# Blueshift_V1.net
KiCad netlist of a schematic drawn in EAGLE
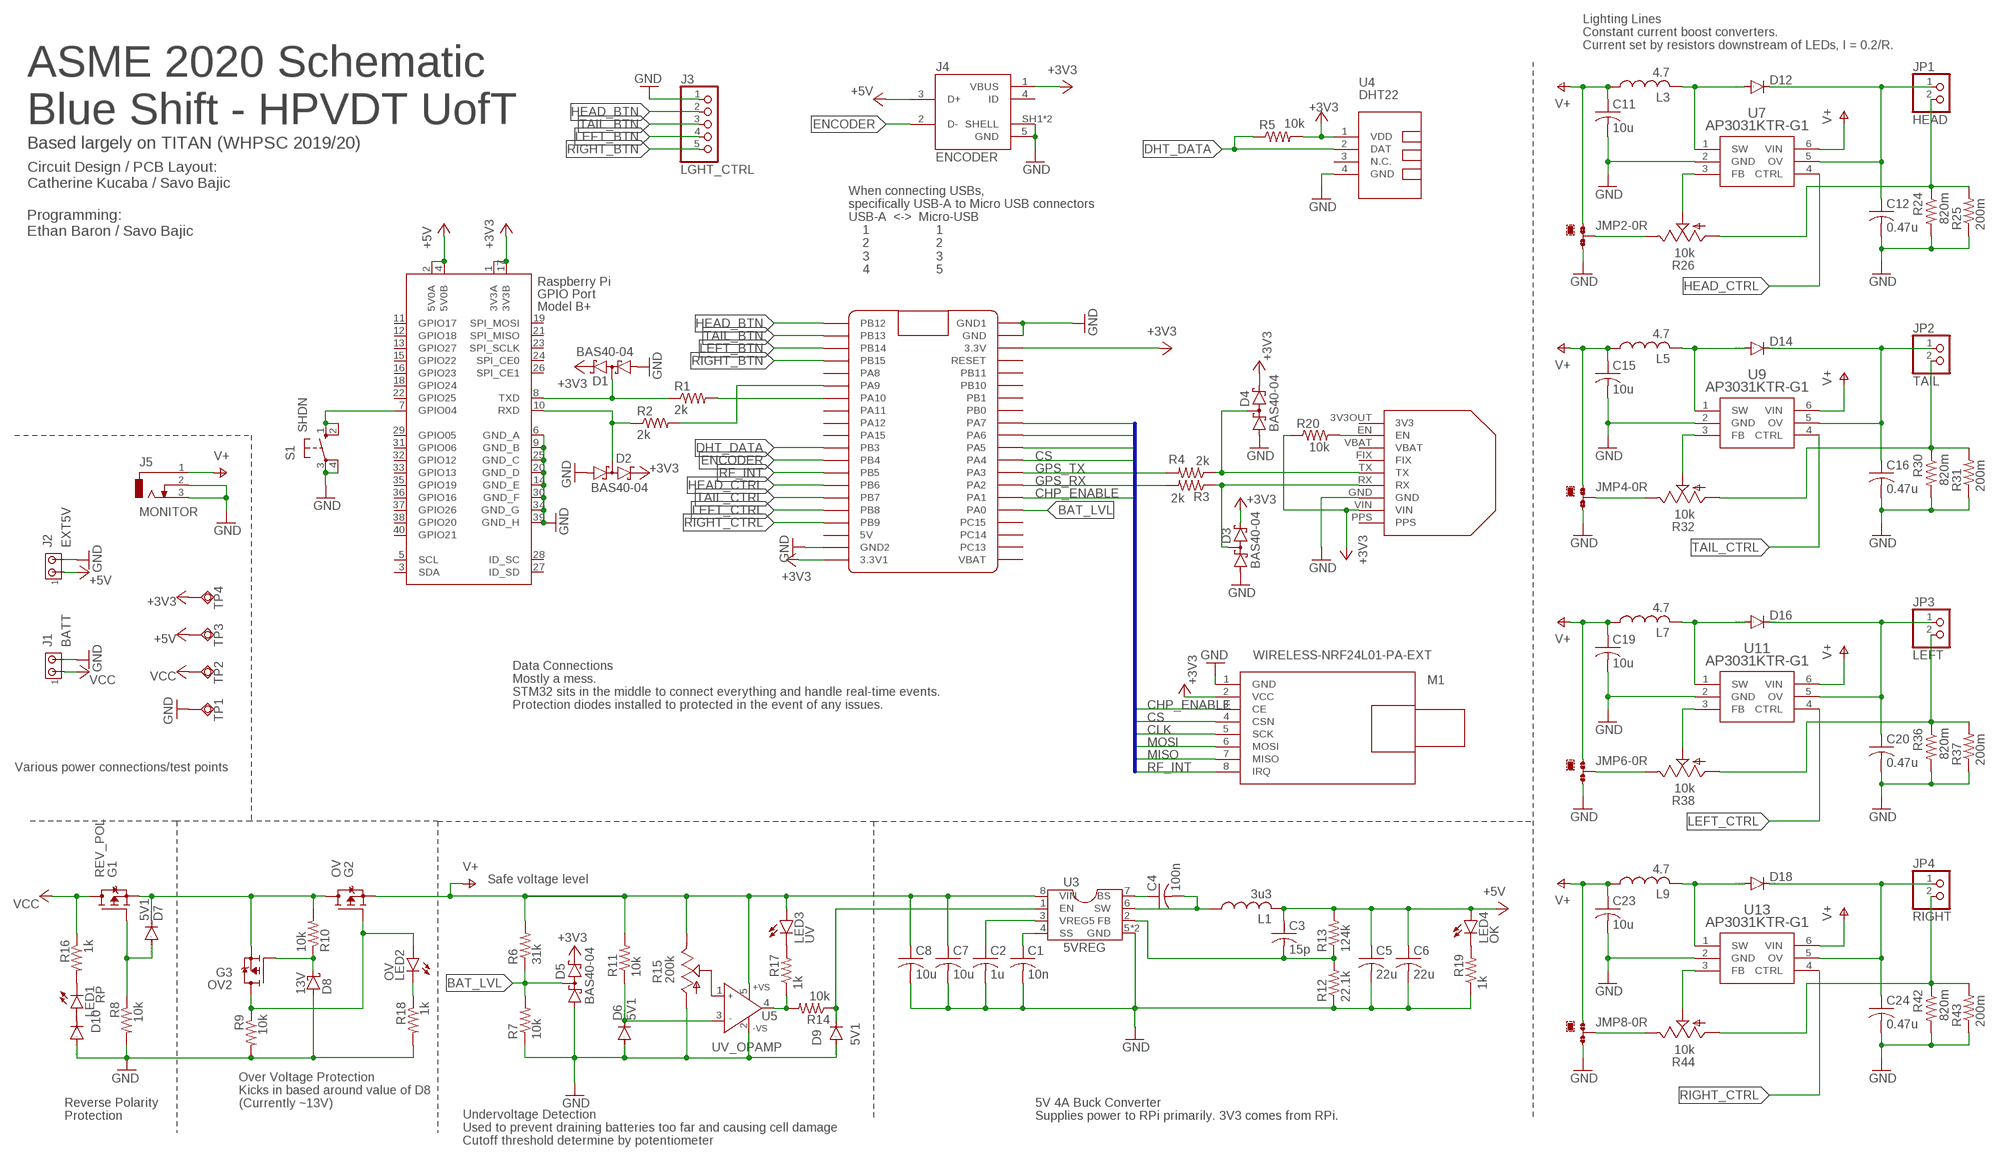
[diagram p0: schematic, sheet 1]

(export (version "E")
  (design (tool "Eeschema 10.0.6"))
  (components
    (comp (ref "C1")
      (value "10n")
      (footprint "eagle-import:C0402")
      (libsource (lib "eagle-import") (part "C-USC0402"))
    )
    (comp (ref "C2")
      (value "1u")
      (footprint "eagle-import:C0402")
      (libsource (lib "eagle-import") (part "C-USC0402"))
    )
    (comp (ref "C3")
      (value "15p")
      (footprint "eagle-import:C0402")
      (libsource (lib "eagle-import") (part "C-USC0402"))
    )
    (comp (ref "C4")
      (value "100n")
      (footprint "eagle-import:C0402")
      (libsource (lib "eagle-import") (part "C-USC0402"))
    )
    (comp (ref "C5")
      (value "22u")
      (footprint "eagle-import:C0805")
      (libsource (lib "eagle-import") (part "C-USC0805"))
    )
    (comp (ref "C6")
      (value "22u")
      (footprint "eagle-import:C0805")
      (libsource (lib "eagle-import") (part "C-USC0805"))
    )
    (comp (ref "C7")
      (value "10u")
      (footprint "eagle-import:C0805")
      (libsource (lib "eagle-import") (part "C-USC0805"))
    )
    (comp (ref "C8")
      (value "10u")
      (footprint "eagle-import:C0805")
      (libsource (lib "eagle-import") (part "C-USC0805"))
    )
    (comp (ref "C11")
      (value "10u")
      (footprint "eagle-import:C1206K")
      (libsource (lib "eagle-import") (part "C-USC1206K"))
    )
    (comp (ref "C12")
      (value "0.47u")
      (footprint "eagle-import:C1206K")
      (libsource (lib "eagle-import") (part "C-USC1206K"))
    )
    (comp (ref "C15")
      (value "10u")
      (footprint "eagle-import:C1206K")
      (libsource (lib "eagle-import") (part "C-USC1206K"))
    )
    (comp (ref "C16")
      (value "0.47u")
      (footprint "eagle-import:C1206K")
      (libsource (lib "eagle-import") (part "C-USC1206K"))
    )
    (comp (ref "C19")
      (value "10u")
      (footprint "eagle-import:C1206K")
      (libsource (lib "eagle-import") (part "C-USC1206K"))
    )
    (comp (ref "C20")
      (value "0.47u")
      (footprint "eagle-import:C1206K")
      (libsource (lib "eagle-import") (part "C-USC1206K"))
    )
    (comp (ref "C23")
      (value "10u")
      (footprint "eagle-import:C1206K")
      (libsource (lib "eagle-import") (part "C-USC1206K"))
    )
    (comp (ref "C24")
      (value "0.47u")
      (footprint "eagle-import:C1206K")
      (libsource (lib "eagle-import") (part "C-USC1206K"))
    )
    (comp (ref "D1")
      (value "BAS40-04")
      (footprint "eagle-import:SOT23")
      (libsource (lib "eagle-import") (part "BAS40-04"))
    )
    (comp (ref "D2")
      (value "BAS40-04")
      (footprint "eagle-import:SOT23")
      (libsource (lib "eagle-import") (part "BAS40-04"))
    )
    (comp (ref "D3")
      (value "BAS40-04")
      (footprint "eagle-import:SOT23")
      (libsource (lib "eagle-import") (part "BAS40-04"))
    )
    (comp (ref "D4")
      (value "BAS40-04")
      (footprint "eagle-import:SOT23")
      (libsource (lib "eagle-import") (part "BAS40-04"))
    )
    (comp (ref "D5")
      (value "BAS40-04")
      (footprint "eagle-import:SOT23")
      (libsource (lib "eagle-import") (part "BAS40-04"))
    )
    (comp (ref "D6")
      (value "5V1")
      (footprint "eagle-import:SOD323-R")
      (libsource (lib "eagle-import") (part "DIODE-SOD323-R"))
    )
    (comp (ref "D7")
      (value "5V1")
      (footprint "eagle-import:SOD323-R")
      (libsource (lib "eagle-import") (part "DIODE-SOD323-R"))
    )
    (comp (ref "D8")
      (value "13V")
      (footprint "eagle-import:SOT23")
      (libsource (lib "eagle-import") (part "BAS70"))
    )
    (comp (ref "D9")
      (value "5V1")
      (footprint "eagle-import:SOD323-R")
      (libsource (lib "eagle-import") (part "DIODE-SOD323-R"))
    )
    (comp (ref "D10")
      (value "DIODE-SOD80C")
      (footprint "eagle-import:SOD80C")
      (libsource (lib "eagle-import") (part "DIODE-SOD80C"))
    )
    (comp (ref "D12")
      (value "DIODE-DO-214AC")
      (footprint "eagle-import:DO-214AC")
      (libsource (lib "eagle-import") (part "DIODE-DO-214AC"))
    )
    (comp (ref "D14")
      (value "DIODE-DO-214AC")
      (footprint "eagle-import:DO-214AC")
      (libsource (lib "eagle-import") (part "DIODE-DO-214AC"))
    )
    (comp (ref "D16")
      (value "DIODE-DO-214AC")
      (footprint "eagle-import:DO-214AC")
      (libsource (lib "eagle-import") (part "DIODE-DO-214AC"))
    )
    (comp (ref "D18")
      (value "DIODE-DO-214AC")
      (footprint "eagle-import:DO-214AC")
      (libsource (lib "eagle-import") (part "DIODE-DO-214AC"))
    )
    (comp (ref "G1")
      (value "REV_POL")
      (footprint "eagle-import:TSOP-6")
      (libsource (lib "eagle-import") (part "SI3493DDV-T1-GE3"))
    )
    (comp (ref "G2")
      (value "OV")
      (footprint "eagle-import:TSOP-6")
      (libsource (lib "eagle-import") (part "SI3493DDV-T1-GE3"))
    )
    (comp (ref "G3")
      (value "OV2")
      (footprint "eagle-import:TSOP-6")
      (libsource (lib "eagle-import") (part "SI3493DDV-T1-GE3"))
    )
    (comp (ref "J1")
      (value "BATT")
      (footprint "eagle-import:1X2MTA")
      (libsource (lib "eagle-import") (part "MTA02-156"))
    )
    (comp (ref "J2")
      (value "EXT5V")
      (footprint "eagle-import:1X2MTA")
      (libsource (lib "eagle-import") (part "MTA02-156"))
    )
    (comp (ref "J3")
      (value "LGHT_CTRL")
      (footprint "eagle-import:1X05")
      (libsource (lib "eagle-import") (part "PINHD-1X5"))
    )
    (comp (ref "J4")
      (value "ENCODER")
      (footprint "eagle-import:TE_2172034-1")
      (fields
        (field (name "COMMENT") "2172034-1")
        (field (name "DIGI-KEY_PART_NUMBER") "A135698-ND")
        (field (name "MF") "TE Connectivity")
      )
      (libsource (lib "eagle-import") (part "2172034-1"))
    )
    (comp (ref "J5")
      (value "MONITOR")
      (footprint "eagle-import:DCJ0303")
      (libsource (lib "eagle-import") (part "DCJ0303"))
    )
    (comp (ref "JMP2")
      (value "0R-JUMPA")
      (footprint "eagle-import:A0R-JMP")
      (libsource (lib "eagle-import") (part "0R-JUMPA"))
    )
    (comp (ref "JMP4")
      (value "0R-JUMPA")
      (footprint "eagle-import:A0R-JMP")
      (libsource (lib "eagle-import") (part "0R-JUMPA"))
    )
    (comp (ref "JMP6")
      (value "0R-JUMPA")
      (footprint "eagle-import:A0R-JMP")
      (libsource (lib "eagle-import") (part "0R-JUMPA"))
    )
    (comp (ref "JMP8")
      (value "0R-JUMPA")
      (footprint "eagle-import:A0R-JMP")
      (libsource (lib "eagle-import") (part "0R-JUMPA"))
    )
    (comp (ref "JP1")
      (value "HEAD")
      (footprint "eagle-import:1X02")
      (libsource (lib "eagle-import") (part "PINHD-1X2"))
    )
    (comp (ref "JP2")
      (value "TAIL")
      (footprint "eagle-import:1X02")
      (libsource (lib "eagle-import") (part "PINHD-1X2"))
    )
    (comp (ref "JP3")
      (value "LEFT")
      (footprint "eagle-import:1X02")
      (libsource (lib "eagle-import") (part "PINHD-1X2"))
    )
    (comp (ref "JP4")
      (value "RIGHT")
      (footprint "eagle-import:1X02")
      (libsource (lib "eagle-import") (part "PINHD-1X2"))
    )
    (comp (ref "L1")
      (value "3u3")
      (footprint "eagle-import:SDES064T")
      (libsource (lib "eagle-import") (part "SDES064T-3R3MS"))
    )
    (comp (ref "L3")
      (value "4.7")
      (footprint "eagle-import:INDDFN600X600X280-2N")
      (libsource (lib "eagle-import") (part "NR6028NR6028"))
    )
    (comp (ref "L5")
      (value "4.7")
      (footprint "eagle-import:INDDFN600X600X280-2N")
      (libsource (lib "eagle-import") (part "NR6028NR6028"))
    )
    (comp (ref "L7")
      (value "4.7")
      (footprint "eagle-import:INDDFN600X600X280-2N")
      (libsource (lib "eagle-import") (part "NR6028NR6028"))
    )
    (comp (ref "L9")
      (value "4.7")
      (footprint "eagle-import:INDDFN600X600X280-2N")
      (libsource (lib "eagle-import") (part "NR6028NR6028"))
    )
    (comp (ref "LED1")
      (value "RP")
      (footprint "eagle-import:SML0805")
      (libsource (lib "eagle-import") (part "LEDSML0805"))
    )
    (comp (ref "LED2")
      (value "OV")
      (footprint "eagle-import:SML0805")
      (libsource (lib "eagle-import") (part "LEDSML0805"))
    )
    (comp (ref "LED3")
      (value "UV")
      (footprint "eagle-import:SML0805")
      (libsource (lib "eagle-import") (part "LEDSML0805"))
    )
    (comp (ref "LED4")
      (value "OK")
      (footprint "eagle-import:SML0805")
      (libsource (lib "eagle-import") (part "LEDSML0805"))
    )
    (comp (ref "M1")
      (value "WIRELESS-NRF24L01-PA-EXT")
      (footprint "eagle-import:WIRELESS-NRF24L01-PA-EXT")
      (libsource (lib "eagle-import") (part "WIRELESS-NRF24L01-PA-EXT"))
    )
    (comp (ref "M2")
      (value "ULTIMATE-GPS")
      (footprint "eagle-import:ULTIMATE_GPS")
      (libsource (lib "eagle-import") (part "ULTIMATE-GPS"))
    )
    (comp (ref "R1")
      (value "2k")
      (footprint "eagle-import:R0402")
      (libsource (lib "eagle-import") (part "R-US_R0402"))
    )
    (comp (ref "R2")
      (value "2k")
      (footprint "eagle-import:R0402")
      (libsource (lib "eagle-import") (part "R-US_R0402"))
    )
    (comp (ref "R3")
      (value "2k")
      (footprint "eagle-import:R0402")
      (libsource (lib "eagle-import") (part "R-US_R0402"))
    )
    (comp (ref "R4")
      (value "2k")
      (footprint "eagle-import:R0402")
      (libsource (lib "eagle-import") (part "R-US_R0402"))
    )
    (comp (ref "R5")
      (value "10k")
      (footprint "eagle-import:R0402")
      (libsource (lib "eagle-import") (part "R-US_R0402"))
    )
    (comp (ref "R6")
      (value "31k")
      (footprint "eagle-import:R0402")
      (libsource (lib "eagle-import") (part "R-US_R0402"))
    )
    (comp (ref "R7")
      (value "10k")
      (footprint "eagle-import:R0402")
      (libsource (lib "eagle-import") (part "R-US_R0402"))
    )
    (comp (ref "R8")
      (value "10k")
      (footprint "eagle-import:R0402")
      (libsource (lib "eagle-import") (part "R-US_R0402"))
    )
    (comp (ref "R9")
      (value "10k")
      (footprint "eagle-import:R0402")
      (libsource (lib "eagle-import") (part "R-US_R0402"))
    )
    (comp (ref "R10")
      (value "10k")
      (footprint "eagle-import:R0402")
      (libsource (lib "eagle-import") (part "R-US_R0402"))
    )
    (comp (ref "R11")
      (value "10k")
      (footprint "eagle-import:R0402")
      (libsource (lib "eagle-import") (part "R-US_R0402"))
    )
    (comp (ref "R12")
      (value "22.1k")
      (footprint "eagle-import:R0402")
      (libsource (lib "eagle-import") (part "R-US_R0402"))
    )
    (comp (ref "R13")
      (value "124k")
      (footprint "eagle-import:R0402")
      (libsource (lib "eagle-import") (part "R-US_R0402"))
    )
    (comp (ref "R14")
      (value "10k")
      (footprint "eagle-import:R0402")
      (libsource (lib "eagle-import") (part "R-US_R0402"))
    )
    (comp (ref "R15")
      (value "200k")
      (footprint "eagle-import:CA6V")
      (libsource (lib "eagle-import") (part "TRIM_US-CA6V"))
    )
    (comp (ref "R16")
      (value "1k")
      (footprint "eagle-import:R0402")
      (libsource (lib "eagle-import") (part "R-US_R0402"))
    )
    (comp (ref "R17")
      (value "1k")
      (footprint "eagle-import:R0402")
      (libsource (lib "eagle-import") (part "R-US_R0402"))
    )
    (comp (ref "R18")
      (value "1k")
      (footprint "eagle-import:R0402")
      (libsource (lib "eagle-import") (part "R-US_R0402"))
    )
    (comp (ref "R19")
      (value "1k")
      (footprint "eagle-import:R0402")
      (libsource (lib "eagle-import") (part "R-US_R0402"))
    )
    (comp (ref "R20")
      (value "10k")
      (footprint "eagle-import:R0402")
      (libsource (lib "eagle-import") (part "R-US_R0402"))
    )
    (comp (ref "R24")
      (value "820m")
      (footprint "eagle-import:R0603")
      (libsource (lib "eagle-import") (part "R-US_R0603"))
    )
    (comp (ref "R25")
      (value "200m")
      (footprint "eagle-import:R0805")
      (libsource (lib "eagle-import") (part "R-US_R0805"))
    )
    (comp (ref "R26")
      (value "10k")
      (footprint "eagle-import:RJ9W")
      (libsource (lib "eagle-import") (part "TRIM_US-RJ9W"))
    )
    (comp (ref "R30")
      (value "820m")
      (footprint "eagle-import:R0603")
      (libsource (lib "eagle-import") (part "R-US_R0603"))
    )
    (comp (ref "R31")
      (value "200m")
      (footprint "eagle-import:R0805")
      (libsource (lib "eagle-import") (part "R-US_R0805"))
    )
    (comp (ref "R32")
      (value "10k")
      (footprint "eagle-import:RJ9W")
      (libsource (lib "eagle-import") (part "TRIM_US-RJ9W"))
    )
    (comp (ref "R36")
      (value "820m")
      (footprint "eagle-import:R0603")
      (libsource (lib "eagle-import") (part "R-US_R0603"))
    )
    (comp (ref "R37")
      (value "200m")
      (footprint "eagle-import:R0805")
      (libsource (lib "eagle-import") (part "R-US_R0805"))
    )
    (comp (ref "R38")
      (value "10k")
      (footprint "eagle-import:RJ9W")
      (libsource (lib "eagle-import") (part "TRIM_US-RJ9W"))
    )
    (comp (ref "R42")
      (value "820m")
      (footprint "eagle-import:R0603")
      (libsource (lib "eagle-import") (part "R-US_R0603"))
    )
    (comp (ref "R43")
      (value "200m")
      (footprint "eagle-import:R0805")
      (libsource (lib "eagle-import") (part "R-US_R0805"))
    )
    (comp (ref "R44")
      (value "10k")
      (footprint "eagle-import:RJ9W")
      (libsource (lib "eagle-import") (part "TRIM_US-RJ9W"))
    )
    (comp (ref "S1")
      (value "SHDN")
      (footprint "eagle-import:B3F-10XX")
      (fields (field (name "MPN") "B3F-1000"))
      (libsource (lib "eagle-import") (part "10-XX"))
    )
    (comp (ref "TP1")
      (value "TPSQTP20SQ")
      (footprint "eagle-import:TP20SQ")
      (libsource (lib "eagle-import") (part "TPSQTP20SQ"))
    )
    (comp (ref "TP2")
      (value "TPSQTP20R")
      (footprint "eagle-import:TP20R")
      (libsource (lib "eagle-import") (part "TPSQTP20R"))
    )
    (comp (ref "TP3")
      (value "TPSQTP20R")
      (footprint "eagle-import:TP20R")
      (libsource (lib "eagle-import") (part "TPSQTP20R"))
    )
    (comp (ref "TP4")
      (value "TPSQTP20R")
      (footprint "eagle-import:TP20R")
      (libsource (lib "eagle-import") (part "TPSQTP20R"))
    )
    (comp (ref "U1")
      (value "RASPI_HAT")
      (footprint "eagle-import:RASPI_BOARD_B+HAT_CF")
      (libsource (lib "eagle-import") (part "RASPI_HAT"))
    )
    (comp (ref "U2")
      (value "BLUEPILL")
      (footprint "eagle-import:BLUE_PILL")
      (libsource (lib "eagle-import") (part "BLUE_PILL"))
    )
    (comp (ref "U3")
      (value "5VREG")
      (footprint "eagle-import:SO-8EP")
      (libsource (lib "eagle-import") (part "AP65450SP-13"))
    )
    (comp (ref "U4")
      (value "DHT22")
      (footprint "eagle-import:TEMP-HUM-SENSOR-DHT22")
      (libsource (lib "eagle-import") (part "TEMP-HUM-SENSOR-DHT22"))
    )
    (comp (ref "U5")
      (value "UV_OPAMP")
      (footprint "eagle-import:SOT-753")
      (libsource (lib "eagle-import") (part "TA75S558F,LF"))
    )
    (comp (ref "U7")
      (value "AP3031KTR-G1")
      (footprint "eagle-import:SOT23-6")
      (fields (field (name "MANUFACTURER_PART_NUMBER") "AP3031KTRG1"))
      (libsource (lib "eagle-import") (part "AP3031KTR-G1"))
    )
    (comp (ref "U9")
      (value "AP3031KTR-G1")
      (footprint "eagle-import:SOT23-6")
      (fields (field (name "MANUFACTURER_PART_NUMBER") "AP3031KTRG1"))
      (libsource (lib "eagle-import") (part "AP3031KTR-G1"))
    )
    (comp (ref "U11")
      (value "AP3031KTR-G1")
      (footprint "eagle-import:SOT23-6")
      (fields (field (name "MANUFACTURER_PART_NUMBER") "AP3031KTRG1"))
      (libsource (lib "eagle-import") (part "AP3031KTR-G1"))
    )
    (comp (ref "U13")
      (value "AP3031KTR-G1")
      (footprint "eagle-import:SOT23-6")
      (fields (field (name "MANUFACTURER_PART_NUMBER") "AP3031KTRG1"))
      (libsource (lib "eagle-import") (part "AP3031KTR-G1"))
    )
  )
  (nets
    (net (code "1") (name "+3V3") (class "Default")
      (node (ref "D1") (pin "2") (pinfunction "C2_2") (pintype "passive"))
      (node (ref "D2") (pin "2") (pinfunction "C2_2") (pintype "passive"))
      (node (ref "D3") (pin "2") (pinfunction "C2_2") (pintype "passive"))
      (node (ref "D4") (pin "2") (pinfunction "C2_2") (pintype "passive"))
      (node (ref "D5") (pin "2") (pinfunction "C2_2") (pintype "passive"))
      (node (ref "J4") (pin "1") (pinfunction "VBUS_1") (pintype "power_in"))
      (node (ref "M1") (pin "2") (pinfunction "VCC_2") (pintype "power_in"))
      (node (ref "M2") (pin "VIN") (pinfunction "VIN_VIN") (pintype "power_in"))
      (node (ref "R20") (pin "1") (pinfunction "1_1") (pintype "passive"))
      (node (ref "R5") (pin "2") (pinfunction "2_2") (pintype "passive"))
      (node (ref "TP4") (pin "TP") (pinfunction "TP_TP") (pintype "input"))
      (node (ref "U1") (pin "1") (pinfunction "3V3A_1") (pintype "power_in"))
      (node (ref "U1") (pin "17") (pinfunction "3V3B_17") (pintype "power_in"))
      (node (ref "U2") (pin "P$20") (pinfunction "3.3V1_P$20") (pintype "bidirectional"))
      (node (ref "U2") (pin "P$23") (pinfunction "3.3V_P$23") (pintype "bidirectional"))
      (node (ref "U4") (pin "1") (pinfunction "VDD_1") (pintype "power_in"))
    )
    (net (code "2") (name "+5V") (class "Default")
      (node (ref "C3") (pin "1") (pinfunction "1_1") (pintype "passive"))
      (node (ref "C5") (pin "1") (pinfunction "1_1") (pintype "passive"))
      (node (ref "C6") (pin "1") (pinfunction "1_1") (pintype "passive"))
      (node (ref "J2") (pin "1") (pinfunction "1_1") (pintype "passive"))
      (node (ref "J4") (pin "3") (pinfunction "D+_3") (pintype "bidirectional"))
      (node (ref "L1") (pin "2") (pinfunction "2_2") (pintype "passive"))
      (node (ref "LED4") (pin "A") (pinfunction "A_A") (pintype "passive"))
      (node (ref "R13") (pin "2") (pinfunction "2_2") (pintype "passive"))
      (node (ref "TP3") (pin "TP") (pinfunction "TP_TP") (pintype "input"))
      (node (ref "U1") (pin "2") (pinfunction "5V0A_2") (pintype "power_in"))
      (node (ref "U1") (pin "4") (pinfunction "5V0B_4") (pintype "power_in"))
    )
    (net (code "3") (name "/CHP_ENABLE") (class "Default")
      (node (ref "M1") (pin "3") (pinfunction "CE_3") (pintype "bidirectional"))
      (node (ref "U2") (pin "P$35") (pinfunction "PA1_P$35") (pintype "bidirectional"))
    )
    (net (code "4") (name "/CLK") (class "Default")
      (node (ref "M1") (pin "5") (pinfunction "SCK_5") (pintype "bidirectional"))
      (node (ref "U2") (pin "P$31") (pinfunction "PA5_P$31") (pintype "bidirectional"))
    )
    (net (code "5") (name "/CS") (class "Default")
      (node (ref "M1") (pin "4") (pinfunction "CSN_4") (pintype "bidirectional"))
      (node (ref "U2") (pin "P$32") (pinfunction "PA4_P$32") (pintype "bidirectional"))
    )
    (net (code "6") (name "/GPS_RX") (class "Default")
      (node (ref "R3") (pin "2") (pinfunction "2_2") (pintype "passive"))
      (node (ref "U2") (pin "P$34") (pinfunction "PA2_P$34") (pintype "bidirectional"))
    )
    (net (code "7") (name "/GPS_TX") (class "Default")
      (node (ref "R4") (pin "2") (pinfunction "2_2") (pintype "passive"))
      (node (ref "U2") (pin "P$33") (pinfunction "PA3_P$33") (pintype "bidirectional"))
    )
    (net (code "8") (name "/MISO") (class "Default")
      (node (ref "M1") (pin "7") (pinfunction "MISO_7") (pintype "bidirectional"))
      (node (ref "U2") (pin "P$30") (pinfunction "PA6_P$30") (pintype "bidirectional"))
    )
    (net (code "9") (name "/MOSI") (class "Default")
      (node (ref "M1") (pin "6") (pinfunction "MOSI_6") (pintype "bidirectional"))
      (node (ref "U2") (pin "P$29") (pinfunction "PA7_P$29") (pintype "bidirectional"))
    )
    (net (code "10") (name "BAT_LVL") (class "Default")
      (node (ref "D5") (pin "3") (pinfunction "C1A2_3") (pintype "passive"))
      (node (ref "R6") (pin "1") (pinfunction "1_1") (pintype "passive"))
      (node (ref "R7") (pin "2") (pinfunction "2_2") (pintype "passive"))
      (node (ref "U2") (pin "P$36") (pinfunction "PA0_P$36") (pintype "bidirectional"))
    )
    (net (code "11") (name "DHT_DATA") (class "Default")
      (node (ref "R5") (pin "1") (pinfunction "1_1") (pintype "passive"))
      (node (ref "U2") (pin "P$11") (pinfunction "PB3_P$11") (pintype "bidirectional"))
      (node (ref "U4") (pin "2") (pinfunction "DAT_2") (pintype "bidirectional"))
    )
    (net (code "12") (name "ENCODER") (class "Default")
      (node (ref "J4") (pin "2") (pinfunction "D-_2") (pintype "bidirectional"))
      (node (ref "U2") (pin "P$12") (pinfunction "PB4_P$12") (pintype "bidirectional"))
    )
    (net (code "13") (name "GND") (class "Default")
      (node (ref "C1") (pin "2") (pinfunction "2_2") (pintype "passive"))
      (node (ref "C11") (pin "2") (pinfunction "2_2") (pintype "passive"))
      (node (ref "C12") (pin "2") (pinfunction "2_2") (pintype "passive"))
      (node (ref "C15") (pin "2") (pinfunction "2_2") (pintype "passive"))
      (node (ref "C16") (pin "2") (pinfunction "2_2") (pintype "passive"))
      (node (ref "C19") (pin "2") (pinfunction "2_2") (pintype "passive"))
      (node (ref "C2") (pin "2") (pinfunction "2_2") (pintype "passive"))
      (node (ref "C20") (pin "2") (pinfunction "2_2") (pintype "passive"))
      (node (ref "C23") (pin "2") (pinfunction "2_2") (pintype "passive"))
      (node (ref "C24") (pin "2") (pinfunction "2_2") (pintype "passive"))
      (node (ref "C5") (pin "2") (pinfunction "2_2") (pintype "passive"))
      (node (ref "C6") (pin "2") (pinfunction "2_2") (pintype "passive"))
      (node (ref "C7") (pin "2") (pinfunction "2_2") (pintype "passive"))
      (node (ref "C8") (pin "2") (pinfunction "2_2") (pintype "passive"))
      (node (ref "D1") (pin "1") (pinfunction "A1_1") (pintype "passive"))
      (node (ref "D10") (pin "A") (pinfunction "A_A") (pintype "passive"))
      (node (ref "D2") (pin "1") (pinfunction "A1_1") (pintype "passive"))
      (node (ref "D3") (pin "1") (pinfunction "A1_1") (pintype "passive"))
      (node (ref "D4") (pin "1") (pinfunction "A1_1") (pintype "passive"))
      (node (ref "D5") (pin "1") (pinfunction "A1_1") (pintype "passive"))
      (node (ref "D6") (pin "A") (pinfunction "A_A") (pintype "passive"))
      (node (ref "D8") (pin "1") (pinfunction "A_1") (pintype "passive"))
      (node (ref "D9") (pin "A") (pinfunction "A_A") (pintype "passive"))
      (node (ref "J1") (pin "2") (pinfunction "2_2") (pintype "passive"))
      (node (ref "J2") (pin "2") (pinfunction "2_2") (pintype "passive"))
      (node (ref "J3") (pin "1") (pinfunction "1_1") (pintype "passive"))
      (node (ref "J4") (pin "5") (pinfunction "GND_5") (pintype "power_in"))
      (node (ref "J4") (pin "SH1") (pinfunction "SHELL_SH1") (pintype "power_in"))
      (node (ref "J4") (pin "SH2") (pinfunction "SHELL_SH2") (pintype "power_in"))
      (node (ref "J5") (pin "2") (pinfunction "2_2") (pintype "passive"))
      (node (ref "J5") (pin "3") (pinfunction "3_3") (pintype "passive"))
      (node (ref "JMP2") (pin "3") (pinfunction "3_3") (pintype "passive"))
      (node (ref "JMP4") (pin "3") (pinfunction "3_3") (pintype "passive"))
      (node (ref "JMP6") (pin "3") (pinfunction "3_3") (pintype "passive"))
      (node (ref "JMP8") (pin "3") (pinfunction "3_3") (pintype "passive"))
      (node (ref "M1") (pin "1") (pinfunction "GND_1") (pintype "power_in"))
      (node (ref "M2") (pin "GND") (pinfunction "GND_GND") (pintype "power_in"))
      (node (ref "R12") (pin "1") (pinfunction "1_1") (pintype "passive"))
      (node (ref "R15") (pin "A") (pinfunction "A_A") (pintype "passive"))
      (node (ref "R18") (pin "2") (pinfunction "2_2") (pintype "passive"))
      (node (ref "R19") (pin "1") (pinfunction "1_1") (pintype "passive"))
      (node (ref "R24") (pin "2") (pinfunction "2_2") (pintype "passive"))
      (node (ref "R25") (pin "1") (pinfunction "1_1") (pintype "passive"))
      (node (ref "R30") (pin "2") (pinfunction "2_2") (pintype "passive"))
      (node (ref "R31") (pin "1") (pinfunction "1_1") (pintype "passive"))
      (node (ref "R36") (pin "2") (pinfunction "2_2") (pintype "passive"))
      (node (ref "R37") (pin "1") (pinfunction "1_1") (pintype "passive"))
      (node (ref "R42") (pin "2") (pinfunction "2_2") (pintype "passive"))
      (node (ref "R43") (pin "1") (pinfunction "1_1") (pintype "passive"))
      (node (ref "R7") (pin "1") (pinfunction "1_1") (pintype "passive"))
      (node (ref "R8") (pin "2") (pinfunction "2_2") (pintype "passive"))
      (node (ref "R9") (pin "2") (pinfunction "2_2") (pintype "passive"))
      (node (ref "S1") (pin "3") (pinfunction "P_3") (pintype "passive"))
      (node (ref "S1") (pin "4") (pinfunction "P1_4") (pintype "passive"))
      (node (ref "TP1") (pin "TP") (pinfunction "TP_TP") (pintype "input"))
      (node (ref "U1") (pin "14") (pinfunction "GND_E_14") (pintype "power_in"))
      (node (ref "U1") (pin "20") (pinfunction "GND_D_20") (pintype "power_in"))
      (node (ref "U1") (pin "25") (pinfunction "GND_C_25") (pintype "power_in"))
      (node (ref "U1") (pin "30") (pinfunction "GND_F_30") (pintype "power_in"))
      (node (ref "U1") (pin "34") (pinfunction "GND_G_34") (pintype "power_in"))
      (node (ref "U1") (pin "39") (pinfunction "GND_H_39") (pintype "power_in"))
      (node (ref "U1") (pin "6") (pinfunction "GND_A_6") (pintype "power_in"))
      (node (ref "U1") (pin "9") (pinfunction "GND_B_9") (pintype "power_in"))
      (node (ref "U11") (pin "2") (pinfunction "GND_2") (pintype "power_in"))
      (node (ref "U13") (pin "2") (pinfunction "GND_2") (pintype "power_in"))
      (node (ref "U2") (pin "P$19") (pinfunction "GND2_P$19") (pintype "bidirectional"))
      (node (ref "U2") (pin "P$21") (pinfunction "GND1_P$21") (pintype "power_in"))
      (node (ref "U2") (pin "P$22") (pinfunction "GND_P$22") (pintype "bidirectional"))
      (node (ref "U3") (pin "5") (pinfunction "GND_5") (pintype "bidirectional"))
      (node (ref "U3") (pin "TP") (pinfunction "GND_TP") (pintype "bidirectional"))
      (node (ref "U4") (pin "4") (pinfunction "GND_4") (pintype "power_in"))
      (node (ref "U5") (pin "2") (pinfunction "-VS_2") (pintype "input"))
      (node (ref "U7") (pin "2") (pinfunction "GND_2") (pintype "power_in"))
      (node (ref "U9") (pin "2") (pinfunction "GND_2") (pintype "power_in"))
    )
    (net (code "14") (name "HEAD_BTN") (class "Default")
      (node (ref "J3") (pin "2") (pinfunction "2_2") (pintype "passive"))
      (node (ref "U2") (pin "P$1") (pinfunction "PB12_P$1") (pintype "bidirectional"))
    )
    (net (code "15") (name "HEAD_CTRL") (class "Default")
      (node (ref "U2") (pin "P$14") (pinfunction "PB6_P$14") (pintype "bidirectional"))
      (node (ref "U7") (pin "4") (pinfunction "CTRL_4") (pintype "passive"))
    )
    (net (code "16") (name "LEFT_BTN") (class "Default")
      (node (ref "J3") (pin "4") (pinfunction "4_4") (pintype "passive"))
      (node (ref "U2") (pin "P$3") (pinfunction "PB14_P$3") (pintype "bidirectional"))
    )
    (net (code "17") (name "LEFT_CTRL") (class "Default")
      (node (ref "U11") (pin "4") (pinfunction "CTRL_4") (pintype "passive"))
      (node (ref "U2") (pin "P$16") (pinfunction "PB8_P$16") (pintype "bidirectional"))
    )
    (net (code "18") (name "Net-(D1-C1A2)") (class "Default")
      (node (ref "D1") (pin "3") (pinfunction "C1A2_3") (pintype "passive"))
      (node (ref "R1") (pin "1") (pinfunction "1_1") (pintype "passive"))
      (node (ref "U1") (pin "8") (pinfunction "TXD_8") (pintype "bidirectional"))
    )
    (net (code "19") (name "Net-(D2-C1A2)") (class "Default")
      (node (ref "D2") (pin "3") (pinfunction "C1A2_3") (pintype "passive"))
      (node (ref "R2") (pin "1") (pinfunction "1_1") (pintype "passive"))
      (node (ref "U1") (pin "10") (pinfunction "RXD_10") (pintype "bidirectional"))
    )
    (net (code "20") (name "Net-(D3-C1A2)") (class "Default")
      (node (ref "D3") (pin "3") (pinfunction "C1A2_3") (pintype "passive"))
      (node (ref "M2") (pin "RX") (pinfunction "RX_RX") (pintype "input"))
      (node (ref "R3") (pin "1") (pinfunction "1_1") (pintype "passive"))
    )
    (net (code "21") (name "Net-(D4-C1A2)") (class "Default")
      (node (ref "D4") (pin "3") (pinfunction "C1A2_3") (pintype "passive"))
      (node (ref "M2") (pin "TX") (pinfunction "TX_TX") (pintype "output"))
      (node (ref "R4") (pin "1") (pinfunction "1_1") (pintype "passive"))
    )
    (net (code "22") (name "Net-(D8-C)") (class "Default")
      (node (ref "D8") (pin "3") (pinfunction "C_3") (pintype "passive"))
      (node (ref "G3") (pin "3") (pinfunction "G_3") (pintype "passive"))
      (node (ref "R10") (pin "1") (pinfunction "1_1") (pintype "passive"))
    )
    (net (code "23") (name "Net-(D10-PadC)") (class "Default")
      (node (ref "D10") (pin "C") (pinfunction "C_C") (pintype "passive"))
      (node (ref "LED1") (pin "A") (pinfunction "A_A") (pintype "passive"))
    )
    (net (code "24") (name "Net-(G1-G)") (class "Default")
      (node (ref "D7") (pin "A") (pinfunction "A_A") (pintype "passive"))
      (node (ref "G1") (pin "3") (pinfunction "G_3") (pintype "passive"))
      (node (ref "R8") (pin "1") (pinfunction "1_1") (pintype "passive"))
    )
    (net (code "25") (name "Net-(G1-S)") (class "Default")
      (node (ref "D7") (pin "C") (pinfunction "C_C") (pintype "passive"))
      (node (ref "G1") (pin "4") (pinfunction "S_4") (pintype "passive"))
      (node (ref "G2") (pin "1") (pinfunction "D_1") (pintype "passive"))
      (node (ref "G2") (pin "2") (pinfunction "D_2") (pintype "passive"))
      (node (ref "G2") (pin "5") (pinfunction "D_5") (pintype "passive"))
      (node (ref "G2") (pin "6") (pinfunction "D_6") (pintype "passive"))
      (node (ref "G3") (pin "4") (pinfunction "S_4") (pintype "passive"))
      (node (ref "R10") (pin "2") (pinfunction "2_2") (pintype "passive"))
    )
    (net (code "26") (name "Net-(G2-G)") (class "Default")
      (node (ref "G2") (pin "3") (pinfunction "G_3") (pintype "passive"))
      (node (ref "G3") (pin "1") (pinfunction "D_1") (pintype "passive"))
      (node (ref "G3") (pin "2") (pinfunction "D_2") (pintype "passive"))
      (node (ref "G3") (pin "5") (pinfunction "D_5") (pintype "passive"))
      (node (ref "G3") (pin "6") (pinfunction "D_6") (pintype "passive"))
      (node (ref "LED2") (pin "A") (pinfunction "A_A") (pintype "passive"))
      (node (ref "R9") (pin "1") (pinfunction "1_1") (pintype "passive"))
    )
    (net (code "27") (name "Net-(JMP2-Pad2)") (class "Default")
      (node (ref "JMP2") (pin "2") (pinfunction "2_2") (pintype "passive"))
      (node (ref "R26") (pin "E") (pinfunction "E_E") (pintype "passive"))
    )
    (net (code "28") (name "Net-(JMP4-Pad2)") (class "Default")
      (node (ref "JMP4") (pin "2") (pinfunction "2_2") (pintype "passive"))
      (node (ref "R32") (pin "E") (pinfunction "E_E") (pintype "passive"))
    )
    (net (code "29") (name "Net-(JMP6-Pad2)") (class "Default")
      (node (ref "JMP6") (pin "2") (pinfunction "2_2") (pintype "passive"))
      (node (ref "R38") (pin "E") (pinfunction "E_E") (pintype "passive"))
    )
    (net (code "30") (name "Net-(JMP8-Pad2)") (class "Default")
      (node (ref "JMP8") (pin "2") (pinfunction "2_2") (pintype "passive"))
      (node (ref "R44") (pin "E") (pinfunction "E_E") (pintype "passive"))
    )
    (net (code "31") (name "Net-(JP1-Pad2)") (class "Default")
      (node (ref "JP1") (pin "2") (pinfunction "2_2") (pintype "passive"))
      (node (ref "R24") (pin "1") (pinfunction "1_1") (pintype "passive"))
      (node (ref "R25") (pin "2") (pinfunction "2_2") (pintype "passive"))
      (node (ref "R26") (pin "A") (pinfunction "A_A") (pintype "passive"))
    )
    (net (code "32") (name "Net-(JP2-Pad2)") (class "Default")
      (node (ref "JP2") (pin "2") (pinfunction "2_2") (pintype "passive"))
      (node (ref "R30") (pin "1") (pinfunction "1_1") (pintype "passive"))
      (node (ref "R31") (pin "2") (pinfunction "2_2") (pintype "passive"))
      (node (ref "R32") (pin "A") (pinfunction "A_A") (pintype "passive"))
    )
    (net (code "33") (name "Net-(JP3-Pad2)") (class "Default")
      (node (ref "JP3") (pin "2") (pinfunction "2_2") (pintype "passive"))
      (node (ref "R36") (pin "1") (pinfunction "1_1") (pintype "passive"))
      (node (ref "R37") (pin "2") (pinfunction "2_2") (pintype "passive"))
      (node (ref "R38") (pin "A") (pinfunction "A_A") (pintype "passive"))
    )
    (net (code "34") (name "Net-(JP4-Pad2)") (class "Default")
      (node (ref "JP4") (pin "2") (pinfunction "2_2") (pintype "passive"))
      (node (ref "R42") (pin "1") (pinfunction "1_1") (pintype "passive"))
      (node (ref "R43") (pin "2") (pinfunction "2_2") (pintype "passive"))
      (node (ref "R44") (pin "A") (pinfunction "A_A") (pintype "passive"))
    )
    (net (code "35") (name "Net-(LED1-PadC)") (class "Default")
      (node (ref "LED1") (pin "C") (pinfunction "C_C") (pintype "passive"))
      (node (ref "R16") (pin "2") (pinfunction "2_2") (pintype "passive"))
    )
    (net (code "36") (name "Net-(LED2-PadC)") (class "Default")
      (node (ref "LED2") (pin "C") (pinfunction "C_C") (pintype "passive"))
      (node (ref "R18") (pin "1") (pinfunction "1_1") (pintype "passive"))
    )
    (net (code "37") (name "Net-(LED3-PadC)") (class "Default")
      (node (ref "LED3") (pin "C") (pinfunction "C_C") (pintype "passive"))
      (node (ref "R17") (pin "2") (pinfunction "2_2") (pintype "passive"))
    )
    (net (code "38") (name "Net-(LED4-PadC)") (class "Default")
      (node (ref "LED4") (pin "C") (pinfunction "C_C") (pintype "passive"))
      (node (ref "R19") (pin "2") (pinfunction "2_2") (pintype "passive"))
    )
    (net (code "39") (name "Net-(M2-PadEN)") (class "Default")
      (node (ref "M2") (pin "EN") (pinfunction "EN_EN") (pintype "input"))
      (node (ref "R20") (pin "2") (pinfunction "2_2") (pintype "passive"))
    )
    (net (code "40") (name "Net-(S1-S)") (class "Default")
      (node (ref "S1") (pin "1") (pinfunction "S_1") (pintype "passive"))
      (node (ref "S1") (pin "2") (pinfunction "S1_2") (pintype "passive"))
      (node (ref "U1") (pin "7") (pinfunction "GPIO04_7") (pintype "bidirectional"))
    )
    (net (code "41") (name "Net-(U2-PA9)") (class "Default")
      (node (ref "R2") (pin "2") (pinfunction "2_2") (pintype "passive"))
      (node (ref "U2") (pin "P$6") (pinfunction "PA9_P$6") (pintype "bidirectional"))
    )
    (net (code "42") (name "Net-(U2-PA10)") (class "Default")
      (node (ref "R1") (pin "2") (pinfunction "2_2") (pintype "passive"))
      (node (ref "U2") (pin "P$7") (pinfunction "PA10_P$7") (pintype "bidirectional"))
    )
    (net (code "43") (name "Net-(U3-BS)") (class "Default")
      (node (ref "C4") (pin "1") (pinfunction "1_1") (pintype "passive"))
      (node (ref "U3") (pin "7") (pinfunction "BS_7") (pintype "bidirectional"))
    )
    (net (code "44") (name "Net-(U3-EN)") (class "Default")
      (node (ref "D9") (pin "C") (pinfunction "C_C") (pintype "passive"))
      (node (ref "R14") (pin "1") (pinfunction "1_1") (pintype "passive"))
      (node (ref "U3") (pin "1") (pinfunction "EN_1") (pintype "bidirectional"))
    )
    (net (code "45") (name "Net-(U3-FB)") (class "Default")
      (node (ref "C3") (pin "2") (pinfunction "2_2") (pintype "passive"))
      (node (ref "R12") (pin "2") (pinfunction "2_2") (pintype "passive"))
      (node (ref "R13") (pin "1") (pinfunction "1_1") (pintype "passive"))
      (node (ref "U3") (pin "2") (pinfunction "FB_2") (pintype "bidirectional"))
    )
    (net (code "46") (name "Net-(U3-SS)") (class "Default")
      (node (ref "C1") (pin "1") (pinfunction "1_1") (pintype "passive"))
      (node (ref "U3") (pin "4") (pinfunction "SS_4") (pintype "bidirectional"))
    )
    (net (code "47") (name "Net-(U3-SW)") (class "Default")
      (node (ref "C4") (pin "2") (pinfunction "2_2") (pintype "passive"))
      (node (ref "L1") (pin "1") (pinfunction "1_1") (pintype "passive"))
      (node (ref "U3") (pin "6") (pinfunction "SW_6") (pintype "bidirectional"))
    )
    (net (code "48") (name "Net-(U3-VREG5)") (class "Default")
      (node (ref "C2") (pin "1") (pinfunction "1_1") (pintype "passive"))
      (node (ref "U3") (pin "3") (pinfunction "VREG5_3") (pintype "bidirectional"))
    )
    (net (code "49") (name "Net-(U5-IN+)") (class "Default")
      (node (ref "R15") (pin "S") (pinfunction "S_S") (pintype "passive"))
      (node (ref "U5") (pin "1") (pinfunction "IN+_1") (pintype "input"))
    )
    (net (code "50") (name "Net-(U5-IN-)") (class "Default")
      (node (ref "D6") (pin "C") (pinfunction "C_C") (pintype "passive"))
      (node (ref "R11") (pin "1") (pinfunction "1_1") (pintype "passive"))
      (node (ref "U5") (pin "3") (pinfunction "IN-_3") (pintype "input"))
    )
    (net (code "51") (name "Net-(U5-OUT)") (class "Default")
      (node (ref "R14") (pin "2") (pinfunction "2_2") (pintype "passive"))
      (node (ref "R17") (pin "1") (pinfunction "1_1") (pintype "passive"))
      (node (ref "U5") (pin "4") (pinfunction "OUT_4") (pintype "output"))
    )
    (net (code "52") (name "Net-(U7-FB)") (class "Default")
      (node (ref "R26") (pin "S") (pinfunction "S_S") (pintype "passive"))
      (node (ref "U7") (pin "3") (pinfunction "FB_3") (pintype "output"))
    )
    (net (code "53") (name "Net-(U7-OV)") (class "Default")
      (node (ref "C12") (pin "1") (pinfunction "1_1") (pintype "passive"))
      (node (ref "D12") (pin "C") (pinfunction "C_C") (pintype "passive"))
      (node (ref "JP1") (pin "1") (pinfunction "1_1") (pintype "passive"))
      (node (ref "U7") (pin "5") (pinfunction "OV_5") (pintype "passive"))
    )
    (net (code "54") (name "Net-(U7-SW)") (class "Default")
      (node (ref "D12") (pin "A") (pinfunction "A_A") (pintype "passive"))
      (node (ref "L3") (pin "2") (pinfunction "2_2") (pintype "passive"))
      (node (ref "U7") (pin "1") (pinfunction "SW_1") (pintype "output"))
    )
    (net (code "55") (name "Net-(U9-FB)") (class "Default")
      (node (ref "R32") (pin "S") (pinfunction "S_S") (pintype "passive"))
      (node (ref "U9") (pin "3") (pinfunction "FB_3") (pintype "output"))
    )
    (net (code "56") (name "Net-(U9-OV)") (class "Default")
      (node (ref "C16") (pin "1") (pinfunction "1_1") (pintype "passive"))
      (node (ref "D14") (pin "C") (pinfunction "C_C") (pintype "passive"))
      (node (ref "JP2") (pin "1") (pinfunction "1_1") (pintype "passive"))
      (node (ref "U9") (pin "5") (pinfunction "OV_5") (pintype "passive"))
    )
    (net (code "57") (name "Net-(U9-SW)") (class "Default")
      (node (ref "D14") (pin "A") (pinfunction "A_A") (pintype "passive"))
      (node (ref "L5") (pin "2") (pinfunction "2_2") (pintype "passive"))
      (node (ref "U9") (pin "1") (pinfunction "SW_1") (pintype "output"))
    )
    (net (code "58") (name "Net-(U11-FB)") (class "Default")
      (node (ref "R38") (pin "S") (pinfunction "S_S") (pintype "passive"))
      (node (ref "U11") (pin "3") (pinfunction "FB_3") (pintype "output"))
    )
    (net (code "59") (name "Net-(U11-OV)") (class "Default")
      (node (ref "C20") (pin "1") (pinfunction "1_1") (pintype "passive"))
      (node (ref "D16") (pin "C") (pinfunction "C_C") (pintype "passive"))
      (node (ref "JP3") (pin "1") (pinfunction "1_1") (pintype "passive"))
      (node (ref "U11") (pin "5") (pinfunction "OV_5") (pintype "passive"))
    )
    (net (code "60") (name "Net-(U11-SW)") (class "Default")
      (node (ref "D16") (pin "A") (pinfunction "A_A") (pintype "passive"))
      (node (ref "L7") (pin "2") (pinfunction "2_2") (pintype "passive"))
      (node (ref "U11") (pin "1") (pinfunction "SW_1") (pintype "output"))
    )
    (net (code "61") (name "Net-(U13-FB)") (class "Default")
      (node (ref "R44") (pin "S") (pinfunction "S_S") (pintype "passive"))
      (node (ref "U13") (pin "3") (pinfunction "FB_3") (pintype "output"))
    )
    (net (code "62") (name "Net-(U13-OV)") (class "Default")
      (node (ref "C24") (pin "1") (pinfunction "1_1") (pintype "passive"))
      (node (ref "D18") (pin "C") (pinfunction "C_C") (pintype "passive"))
      (node (ref "JP4") (pin "1") (pinfunction "1_1") (pintype "passive"))
      (node (ref "U13") (pin "5") (pinfunction "OV_5") (pintype "passive"))
    )
    (net (code "63") (name "Net-(U13-SW)") (class "Default")
      (node (ref "D18") (pin "A") (pinfunction "A_A") (pintype "passive"))
      (node (ref "L9") (pin "2") (pinfunction "2_2") (pintype "passive"))
      (node (ref "U13") (pin "1") (pinfunction "SW_1") (pintype "output"))
    )
    (net (code "64") (name "RF_INT") (class "Default")
      (node (ref "M1") (pin "8") (pinfunction "IRQ_8") (pintype "bidirectional"))
      (node (ref "U2") (pin "P$13") (pinfunction "PB5_P$13") (pintype "bidirectional"))
    )
    (net (code "65") (name "RIGHT_BTN") (class "Default")
      (node (ref "J3") (pin "5") (pinfunction "5_5") (pintype "passive"))
      (node (ref "U2") (pin "P$4") (pinfunction "PB15_P$4") (pintype "bidirectional"))
    )
    (net (code "66") (name "RIGHT_CTRL") (class "Default")
      (node (ref "U13") (pin "4") (pinfunction "CTRL_4") (pintype "passive"))
      (node (ref "U2") (pin "P$17") (pinfunction "PB9_P$17") (pintype "bidirectional"))
    )
    (net (code "67") (name "TAIL_BTN") (class "Default")
      (node (ref "J3") (pin "3") (pinfunction "3_3") (pintype "passive"))
      (node (ref "U2") (pin "P$2") (pinfunction "PB13_P$2") (pintype "bidirectional"))
    )
    (net (code "68") (name "TAIL_CTRL") (class "Default")
      (node (ref "U2") (pin "P$15") (pinfunction "PB7_P$15") (pintype "bidirectional"))
      (node (ref "U9") (pin "4") (pinfunction "CTRL_4") (pintype "passive"))
    )
    (net (code "69") (name "V+") (class "Default")
      (node (ref "C11") (pin "1") (pinfunction "1_1") (pintype "passive"))
      (node (ref "C15") (pin "1") (pinfunction "1_1") (pintype "passive"))
      (node (ref "C19") (pin "1") (pinfunction "1_1") (pintype "passive"))
      (node (ref "C23") (pin "1") (pinfunction "1_1") (pintype "passive"))
      (node (ref "C7") (pin "1") (pinfunction "1_1") (pintype "passive"))
      (node (ref "C8") (pin "1") (pinfunction "1_1") (pintype "passive"))
      (node (ref "G2") (pin "4") (pinfunction "S_4") (pintype "passive"))
      (node (ref "J5") (pin "1") (pinfunction "1_1") (pintype "passive"))
      (node (ref "JMP2") (pin "1") (pinfunction "1_1") (pintype "passive"))
      (node (ref "JMP4") (pin "1") (pinfunction "1_1") (pintype "passive"))
      (node (ref "JMP6") (pin "1") (pinfunction "1_1") (pintype "passive"))
      (node (ref "JMP8") (pin "1") (pinfunction "1_1") (pintype "passive"))
      (node (ref "L3") (pin "1") (pinfunction "1_1") (pintype "passive"))
      (node (ref "L5") (pin "1") (pinfunction "1_1") (pintype "passive"))
      (node (ref "L7") (pin "1") (pinfunction "1_1") (pintype "passive"))
      (node (ref "L9") (pin "1") (pinfunction "1_1") (pintype "passive"))
      (node (ref "LED3") (pin "A") (pinfunction "A_A") (pintype "passive"))
      (node (ref "R11") (pin "2") (pinfunction "2_2") (pintype "passive"))
      (node (ref "R15") (pin "E") (pinfunction "E_E") (pintype "passive"))
      (node (ref "R6") (pin "2") (pinfunction "2_2") (pintype "passive"))
      (node (ref "U11") (pin "6") (pinfunction "VIN_6") (pintype "input"))
      (node (ref "U13") (pin "6") (pinfunction "VIN_6") (pintype "input"))
      (node (ref "U3") (pin "8") (pinfunction "VIN_8") (pintype "bidirectional"))
      (node (ref "U5") (pin "5") (pinfunction "+VS_5") (pintype "input"))
      (node (ref "U7") (pin "6") (pinfunction "VIN_6") (pintype "input"))
      (node (ref "U9") (pin "6") (pinfunction "VIN_6") (pintype "input"))
    )
    (net (code "70") (name "VCC") (class "Default")
      (node (ref "G1") (pin "1") (pinfunction "D_1") (pintype "passive"))
      (node (ref "G1") (pin "2") (pinfunction "D_2") (pintype "passive"))
      (node (ref "G1") (pin "5") (pinfunction "D_5") (pintype "passive"))
      (node (ref "G1") (pin "6") (pinfunction "D_6") (pintype "passive"))
      (node (ref "J1") (pin "1") (pinfunction "1_1") (pintype "passive"))
      (node (ref "R16") (pin "1") (pinfunction "1_1") (pintype "passive"))
      (node (ref "TP2") (pin "TP") (pinfunction "TP_TP") (pintype "input"))
    )
    (net (code "71") (name "unconnected-(J4-ID-Pad4)") (class "Default")
      (node (ref "J4") (pin "4") (pinfunction "ID_4") (pintype "passive"))
    )
    (net (code "72") (name "unconnected-(M2-3V3-Pad3V3OUT)") (class "Default")
      (node (ref "M2") (pin "3V3OUT") (pinfunction "3V3_3V3OUT") (pintype "output"))
    )
    (net (code "73") (name "unconnected-(M2-PadFIX)") (class "Default")
      (node (ref "M2") (pin "FIX") (pinfunction "FIX_FIX") (pintype "output"))
    )
    (net (code "74") (name "unconnected-(M2-PadPPS)") (class "Default")
      (node (ref "M2") (pin "PPS") (pinfunction "PPS_PPS") (pintype "output"))
    )
    (net (code "75") (name "unconnected-(M2-PadVBAT)") (class "Default")
      (node (ref "M2") (pin "VBAT") (pinfunction "VBAT_VBAT") (pintype "bidirectional"))
    )
    (net (code "76") (name "unconnected-(U1-GPIO05-Pad29)") (class "Default")
      (node (ref "U1") (pin "29") (pinfunction "GPIO05_29") (pintype "bidirectional"))
    )
    (net (code "77") (name "unconnected-(U1-GPIO06-Pad31)") (class "Default")
      (node (ref "U1") (pin "31") (pinfunction "GPIO06_31") (pintype "bidirectional"))
    )
    (net (code "78") (name "unconnected-(U1-GPIO12-Pad32)") (class "Default")
      (node (ref "U1") (pin "32") (pinfunction "GPIO12_32") (pintype "bidirectional"))
    )
    (net (code "79") (name "unconnected-(U1-GPIO13-Pad33)") (class "Default")
      (node (ref "U1") (pin "33") (pinfunction "GPIO13_33") (pintype "bidirectional"))
    )
    (net (code "80") (name "unconnected-(U1-GPIO16-Pad36)") (class "Default")
      (node (ref "U1") (pin "36") (pinfunction "GPIO16_36") (pintype "bidirectional"))
    )
    (net (code "81") (name "unconnected-(U1-GPIO17-Pad11)") (class "Default")
      (node (ref "U1") (pin "11") (pinfunction "GPIO17_11") (pintype "bidirectional"))
    )
    (net (code "82") (name "unconnected-(U1-GPIO18-Pad12)") (class "Default")
      (node (ref "U1") (pin "12") (pinfunction "GPIO18_12") (pintype "bidirectional"))
    )
    (net (code "83") (name "unconnected-(U1-GPIO19-Pad35)") (class "Default")
      (node (ref "U1") (pin "35") (pinfunction "GPIO19_35") (pintype "bidirectional"))
    )
    (net (code "84") (name "unconnected-(U1-GPIO20-Pad38)") (class "Default")
      (node (ref "U1") (pin "38") (pinfunction "GPIO20_38") (pintype "bidirectional"))
    )
    (net (code "85") (name "unconnected-(U1-GPIO21-Pad40)") (class "Default")
      (node (ref "U1") (pin "40") (pinfunction "GPIO21_40") (pintype "bidirectional"))
    )
    (net (code "86") (name "unconnected-(U1-GPIO22-Pad15)") (class "Default")
      (node (ref "U1") (pin "15") (pinfunction "GPIO22_15") (pintype "bidirectional"))
    )
    (net (code "87") (name "unconnected-(U1-GPIO23-Pad16)") (class "Default")
      (node (ref "U1") (pin "16") (pinfunction "GPIO23_16") (pintype "bidirectional"))
    )
    (net (code "88") (name "unconnected-(U1-GPIO24-Pad18)") (class "Default")
      (node (ref "U1") (pin "18") (pinfunction "GPIO24_18") (pintype "bidirectional"))
    )
    (net (code "89") (name "unconnected-(U1-GPIO25-Pad22)") (class "Default")
      (node (ref "U1") (pin "22") (pinfunction "GPIO25_22") (pintype "bidirectional"))
    )
    (net (code "90") (name "unconnected-(U1-GPIO26-Pad37)") (class "Default")
      (node (ref "U1") (pin "37") (pinfunction "GPIO26_37") (pintype "bidirectional"))
    )
    (net (code "91") (name "unconnected-(U1-GPIO27-Pad13)") (class "Default")
      (node (ref "U1") (pin "13") (pinfunction "GPIO27_13") (pintype "bidirectional"))
    )
    (net (code "92") (name "unconnected-(U1-ID_SC-Pad28)") (class "Default")
      (node (ref "U1") (pin "28") (pinfunction "ID_SC_28") (pintype "no_connect"))
    )
    (net (code "93") (name "unconnected-(U1-ID_SD-Pad27)") (class "Default")
      (node (ref "U1") (pin "27") (pinfunction "ID_SD_27") (pintype "no_connect"))
    )
    (net (code "94") (name "unconnected-(U1-SCL-Pad5)") (class "Default")
      (node (ref "U1") (pin "5") (pinfunction "SCL_5") (pintype "bidirectional"))
    )
    (net (code "95") (name "unconnected-(U1-SDA-Pad3)") (class "Default")
      (node (ref "U1") (pin "3") (pinfunction "SDA_3") (pintype "bidirectional"))
    )
    (net (code "96") (name "unconnected-(U1-SPI_CE0-Pad24)") (class "Default")
      (node (ref "U1") (pin "24") (pinfunction "SPI_CE0_24") (pintype "bidirectional"))
    )
    (net (code "97") (name "unconnected-(U1-SPI_CE1-Pad26)") (class "Default")
      (node (ref "U1") (pin "26") (pinfunction "SPI_CE1_26") (pintype "bidirectional"))
    )
    (net (code "98") (name "unconnected-(U1-SPI_MISO-Pad21)") (class "Default")
      (node (ref "U1") (pin "21") (pinfunction "SPI_MISO_21") (pintype "bidirectional"))
    )
    (net (code "99") (name "unconnected-(U1-SPI_MOSI-Pad19)") (class "Default")
      (node (ref "U1") (pin "19") (pinfunction "SPI_MOSI_19") (pintype "bidirectional"))
    )
    (net (code "100") (name "unconnected-(U1-SPI_SCLK-Pad23)") (class "Default")
      (node (ref "U1") (pin "23") (pinfunction "SPI_SCLK_23") (pintype "bidirectional"))
    )
    (net (code "101") (name "unconnected-(U2-5V-PadP$18)") (class "Default")
      (node (ref "U2") (pin "P$18") (pinfunction "5V_P$18") (pintype "bidirectional"))
    )
    (net (code "102") (name "unconnected-(U2-PA8-PadP$5)") (class "Default")
      (node (ref "U2") (pin "P$5") (pinfunction "PA8_P$5") (pintype "bidirectional"))
    )
    (net (code "103") (name "unconnected-(U2-PA11-PadP$8)") (class "Default")
      (node (ref "U2") (pin "P$8") (pinfunction "PA11_P$8") (pintype "bidirectional"))
    )
    (net (code "104") (name "unconnected-(U2-PA12-PadP$9)") (class "Default")
      (node (ref "U2") (pin "P$9") (pinfunction "PA12_P$9") (pintype "bidirectional"))
    )
    (net (code "105") (name "unconnected-(U2-PA15-PadP$10)") (class "Default")
      (node (ref "U2") (pin "P$10") (pinfunction "PA15_P$10") (pintype "bidirectional"))
    )
    (net (code "106") (name "unconnected-(U2-PB0-PadP$28)") (class "Default")
      (node (ref "U2") (pin "P$28") (pinfunction "PB0_P$28") (pintype "bidirectional"))
    )
    (net (code "107") (name "unconnected-(U2-PB1-PadP$27)") (class "Default")
      (node (ref "U2") (pin "P$27") (pinfunction "PB1_P$27") (pintype "bidirectional"))
    )
    (net (code "108") (name "unconnected-(U2-PB10-PadP$26)") (class "Default")
      (node (ref "U2") (pin "P$26") (pinfunction "PB10_P$26") (pintype "bidirectional"))
    )
    (net (code "109") (name "unconnected-(U2-PB11-PadP$25)") (class "Default")
      (node (ref "U2") (pin "P$25") (pinfunction "PB11_P$25") (pintype "bidirectional"))
    )
    (net (code "110") (name "unconnected-(U2-PC13-PadP$39)") (class "Default")
      (node (ref "U2") (pin "P$39") (pinfunction "PC13_P$39") (pintype "bidirectional"))
    )
    (net (code "111") (name "unconnected-(U2-PC14-PadP$38)") (class "Default")
      (node (ref "U2") (pin "P$38") (pinfunction "PC14_P$38") (pintype "bidirectional"))
    )
    (net (code "112") (name "unconnected-(U2-PC15-PadP$37)") (class "Default")
      (node (ref "U2") (pin "P$37") (pinfunction "PC15_P$37") (pintype "bidirectional"))
    )
    (net (code "113") (name "unconnected-(U2-RESET-PadP$24)") (class "Default")
      (node (ref "U2") (pin "P$24") (pinfunction "RESET_P$24") (pintype "bidirectional"))
    )
    (net (code "114") (name "unconnected-(U2-VBAT-PadP$40)") (class "Default")
      (node (ref "U2") (pin "P$40") (pinfunction "VBAT_P$40") (pintype "bidirectional"))
    )
    (net (code "115") (name "unconnected-(U4-N.C.-Pad3)") (class "Default")
      (node (ref "U4") (pin "3") (pinfunction "N.C._3") (pintype "passive"))
    )
  )
)
